# WT-312.net
KiCad netlist of a schematic drawn in Altium Designer
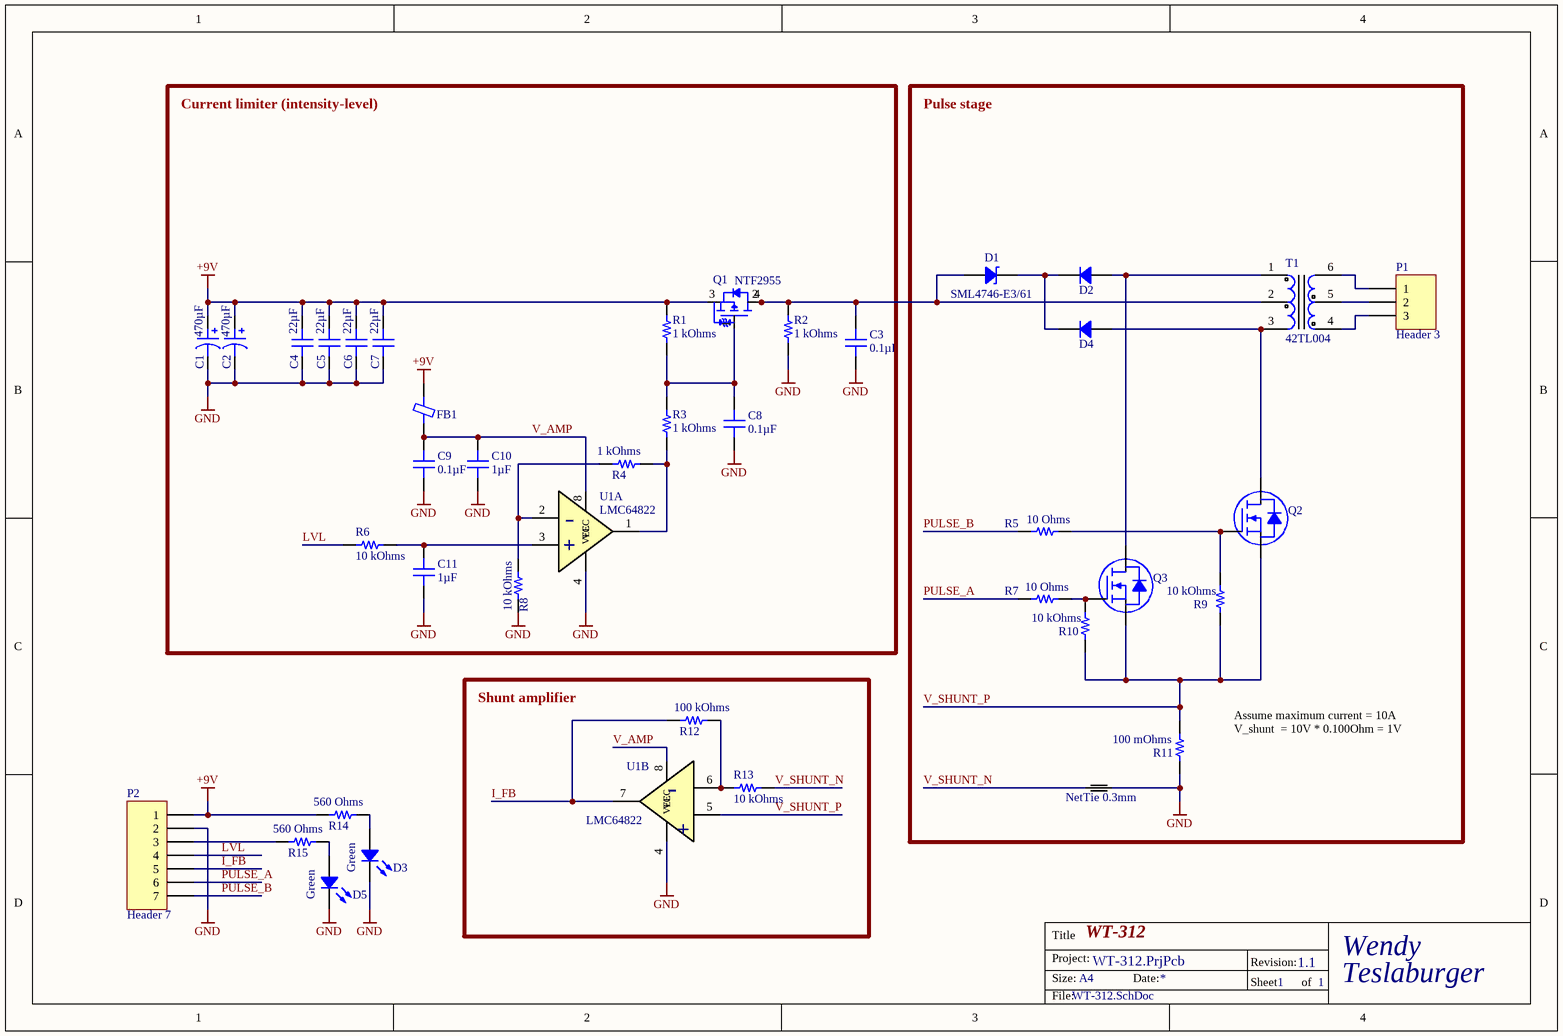
[diagram p0: WT-312.SchDoc]

(export (version "E")
  (design (tool "Eeschema 10.0.6"))
  (components
    (comp (ref "C1")
      (value "470µF")
      (footprint "CAP TH ALUM ELEC D8.00mm S3.50mm H13.00mm")
      (description "CAP ALUM 470UF 20% 16V RADIAL")
      (fields (field (name "PART NUMBER") "477CKE016M") (field (name "MANUFACTURER") "Illinois Capacitor"))
      (libsource (lib "Celestial Altium Library") (part "Polarised Capacitor"))
    )
    (comp (ref "C2")
      (value "470µF")
      (footprint "CAP TH ALUM ELEC D8.00mm S3.50mm H13.00mm")
      (description "CAP ALUM 470UF 20% 16V RADIAL")
      (fields (field (name "PART NUMBER") "477CKE016M") (field (name "MANUFACTURER") "Illinois Capacitor"))
      (libsource (lib "Celestial Altium Library") (part "Polarised Capacitor"))
    )
    (comp (ref "C3")
      (value "0.1µF")
      (footprint "CAP 0603_1608")
      (description "CAP CER 0.1UF 50V X7R 0603")
      (fields (field (name "PART NUMBER") "C0603C104K5RAC7411") (field (name "MANUFACTURER") "KEMET"))
      (libsource (lib "Celestial Altium Library") (part "Capacitor"))
    )
    (comp (ref "C4")
      (value "22µF")
      (footprint "CAP 1210_3225 - 2.8MM")
      (description "CAP CER 22UF 25V X5R 1210")
      (fields (field (name "PART NUMBER") "TMK325BJ226MM-T") (field (name "MANUFACTURER") "Taiyo Yuden"))
      (libsource (lib "Celestial Altium Library") (part "Capacitor"))
    )
    (comp (ref "C5")
      (value "22µF")
      (footprint "CAP 1210_3225 - 2.8MM")
      (description "CAP CER 22UF 25V X5R 1210")
      (fields (field (name "PART NUMBER") "TMK325BJ226MM-T") (field (name "MANUFACTURER") "Taiyo Yuden"))
      (libsource (lib "Celestial Altium Library") (part "Capacitor"))
    )
    (comp (ref "C6")
      (value "22µF")
      (footprint "CAP 1210_3225 - 2.8MM")
      (description "CAP CER 22UF 25V X5R 1210")
      (fields (field (name "PART NUMBER") "TMK325BJ226MM-T") (field (name "MANUFACTURER") "Taiyo Yuden"))
      (libsource (lib "Celestial Altium Library") (part "Capacitor"))
    )
    (comp (ref "C7")
      (value "22µF")
      (footprint "CAP 1210_3225 - 2.8MM")
      (description "CAP CER 22UF 25V X5R 1210")
      (fields (field (name "PART NUMBER") "TMK325BJ226MM-T") (field (name "MANUFACTURER") "Taiyo Yuden"))
      (libsource (lib "Celestial Altium Library") (part "Capacitor"))
    )
    (comp (ref "C8")
      (value "0.1µF")
      (footprint "CAP 0603_1608")
      (description "CAP CER 0.1UF 50V X7R 0603")
      (fields (field (name "PART NUMBER") "C0603C104K5RAC7411") (field (name "MANUFACTURER") "KEMET"))
      (libsource (lib "Celestial Altium Library") (part "Capacitor"))
    )
    (comp (ref "C9")
      (value "0.1µF")
      (footprint "CAP 0603_1608")
      (description "CAP CER 0.1UF 50V X7R 0603")
      (fields (field (name "PART NUMBER") "C0603C104K5RAC7411") (field (name "MANUFACTURER") "KEMET"))
      (libsource (lib "Celestial Altium Library") (part "Capacitor"))
    )
    (comp (ref "C10")
      (value "1µF")
      (footprint "CAP 0603_1608")
      (description "CAP CER 1UF 25V X7R 0603")
      (fields (field (name "PART NUMBER") "TMJ107CB7105KAHR") (field (name "MANUFACTURER") "Taiyo Yuden"))
      (libsource (lib "Celestial Altium Library") (part "Capacitor"))
    )
    (comp (ref "C11")
      (value "1µF")
      (footprint "CAP 0603_1608")
      (description "CAP CER 1UF 25V X7R 0603")
      (fields (field (name "PART NUMBER") "TMJ107CB7105KAHR") (field (name "MANUFACTURER") "Taiyo Yuden"))
      (libsource (lib "Celestial Altium Library") (part "Capacitor"))
    )
    (comp (ref "D1")
      (value "SML4746-E3/61")
      (footprint "DO214AC SMA")
      (description "DIODE ZENER 18V 1W DO214AC")
      (fields
        (field (name "MANUFACTURER") "Vishay Semiconductor Diodes Division")
        (field (name "TOLERANCE") "±10%")
      )
      (libsource (lib "Celestial Altium Library") (part "Diode Zener"))
    )
    (comp (ref "D2")
      (value "DSS14UTR")
      (footprint "SOD123F")
      (description "SCHOTTKY 40V SOD-123FL")
      (fields (field (name "MANUFACTURER") "SMC Diode Solutions"))
      (libsource (lib "Celestial Altium Library") (part "Diode"))
    )
    (comp (ref "D3")
      (value "Green")
      (footprint "LED 1206_3216 GREEN")
      (description "LED GREEN CLEAR 2SMD")
      (fields (field (name "PART NUMBER") "APTD3216LCGCK") (field (name "MANUFACTURER") "Kingbright"))
      (libsource (lib "Celestial Altium Library") (part "LED"))
    )
    (comp (ref "D4")
      (value "DSS14UTR")
      (footprint "SOD123F")
      (description "SCHOTTKY 40V SOD-123FL")
      (fields (field (name "MANUFACTURER") "SMC Diode Solutions"))
      (libsource (lib "Celestial Altium Library") (part "Diode"))
    )
    (comp (ref "D5")
      (value "Green")
      (footprint "LED 1206_3216 GREEN")
      (description "LED GREEN CLEAR 2SMD")
      (fields (field (name "PART NUMBER") "APTD3216LCGCK") (field (name "MANUFACTURER") "Kingbright"))
      (libsource (lib "Celestial Altium Library") (part "LED"))
    )
    (comp (ref "FB1")
      (value "100 Ohms @ 100MHz")
      (footprint "FER 0603_1608")
      (description "FERRITE BEAD 100 OHM 0603 1LN")
      (fields
        (field (name "PART NUMBER") "BLM18KG101TN1D")
        (field (name "MANUFACTURER") "Murata Electronics")
      )
      (libsource (lib "Celestial Altium Library") (part "Ferrite Chip"))
    )
    (comp (ref "NT")
      (value "NetTie 0.3mm")
      (footprint "NetTie0.3mm")
      (libsource (lib "7c7_Passives") (part "NetTie_0.3mm"))
    )
    (comp (ref "P1")
      (value "Header 3")
      (footprint "HDR1X3")
      (description "Header, 3-Pin")
      (fields (field (name "PUBLISHER") "Altium Limited"))
      (libsource (lib "Miscellaneous Connectors") (part "Header 3"))
    )
    (comp (ref "P2")
      (value "Header 7")
      (footprint "HDR1X7")
      (description "Header, 7-Pin")
      (fields (field (name "PUBLISHER") "Altium Limited"))
      (libsource (lib "Miscellaneous Connectors") (part "Header 7"))
    )
    (comp (ref "Q1")
      (value "NTF2955")
      (footprint "SOT230P700X175-4N")
      (description "Single, P-Channel, SOT-223 -60 V, -2.6 A")
      (libsource (lib "7c7_discretes") (part "NTF2955"))
    )
    (comp (ref "Q2")
      (value "DMN2041L-7")
      (footprint "DIODES SOT-23-3")
      (description "MOSFET N-CH 20V 6.4A SOT23")
      (fields (field (name "MANUFACTURER") "Diodes Incorporated"))
      (libsource (lib "Celestial Altium Library") (part "DIODES INC MOSFET N-CH SOT-23-3"))
    )
    (comp (ref "Q3")
      (value "DMN2041L-7")
      (footprint "DIODES SOT-23-3")
      (description "MOSFET N-CH 20V 6.4A SOT23")
      (fields (field (name "MANUFACTURER") "Diodes Incorporated"))
      (libsource (lib "Celestial Altium Library") (part "DIODES INC MOSFET N-CH SOT-23-3"))
    )
    (comp (ref "R1")
      (value "1 kOhms")
      (footprint "RES 0603_1608")
      (description "RES SMD 1K OHM 1% 1/10W 0603")
      (fields (field (name "PART NUMBER") "CRCW06031K00FKTA") (field (name "MANUFACTURER") "Vishay Dale"))
      (libsource (lib "Celestial Altium Library") (part "Resistor"))
    )
    (comp (ref "R2")
      (value "1 kOhms")
      (footprint "RES 0603_1608")
      (description "RES SMD 1K OHM 1% 1/10W 0603")
      (fields (field (name "PART NUMBER") "CRCW06031K00FKTA") (field (name "MANUFACTURER") "Vishay Dale"))
      (libsource (lib "Celestial Altium Library") (part "Resistor"))
    )
    (comp (ref "R3")
      (value "1 kOhms")
      (footprint "RES 0603_1608")
      (description "RES SMD 1K OHM 1% 1/10W 0603")
      (fields (field (name "PART NUMBER") "CRCW06031K00FKTA") (field (name "MANUFACTURER") "Vishay Dale"))
      (libsource (lib "Celestial Altium Library") (part "Resistor"))
    )
    (comp (ref "R4")
      (value "1 kOhms")
      (footprint "RES 0603_1608")
      (description "RES SMD 1K OHM 1% 1/10W 0603")
      (fields (field (name "PART NUMBER") "CRCW06031K00FKTA") (field (name "MANUFACTURER") "Vishay Dale"))
      (libsource (lib "Celestial Altium Library") (part "Resistor"))
    )
    (comp (ref "R5")
      (value "10 Ohms")
      (footprint "RES 0603_1608")
      (description "RES SMD 10 OHM 1% 1/10W 0603")
      (fields (field (name "PART NUMBER") "AC0603FR-0710RL") (field (name "MANUFACTURER") "Yageo"))
      (libsource (lib "Celestial Altium Library") (part "Resistor"))
    )
    (comp (ref "R6")
      (value "10 kOhms")
      (footprint "RES 0603_1608")
      (description "RES 10K OHM 1% 1/10W 0603")
      (fields
        (field (name "PART NUMBER") "RN73H1JTTD1002F100")
        (field (name "MANUFACTURER") "KOA Speer Electronics, Inc.")
      )
      (libsource (lib "Celestial Altium Library") (part "Resistor"))
    )
    (comp (ref "R7")
      (value "10 Ohms")
      (footprint "RES 0603_1608")
      (description "RES SMD 10 OHM 1% 1/10W 0603")
      (fields (field (name "PART NUMBER") "AC0603FR-0710RL") (field (name "MANUFACTURER") "Yageo"))
      (libsource (lib "Celestial Altium Library") (part "Resistor"))
    )
    (comp (ref "R8")
      (value "10 kOhms")
      (footprint "RES 0603_1608")
      (description "RES 10K OHM 1% 1/10W 0603")
      (fields
        (field (name "PART NUMBER") "RN73H1JTTD1002F100")
        (field (name "MANUFACTURER") "KOA Speer Electronics, Inc.")
      )
      (libsource (lib "Celestial Altium Library") (part "Resistor"))
    )
    (comp (ref "R9")
      (value "10 kOhms")
      (footprint "RES 0603_1608")
      (description "RES 10K OHM 1% 1/10W 0603")
      (fields
        (field (name "PART NUMBER") "RN73H1JTTD1002F100")
        (field (name "MANUFACTURER") "KOA Speer Electronics, Inc.")
      )
      (libsource (lib "Celestial Altium Library") (part "Resistor"))
    )
    (comp (ref "R10")
      (value "10 kOhms")
      (footprint "RES 0603_1608")
      (description "RES 10K OHM 1% 1/10W 0603")
      (fields
        (field (name "PART NUMBER") "RN73H1JTTD1002F100")
        (field (name "MANUFACTURER") "KOA Speer Electronics, Inc.")
      )
      (libsource (lib "Celestial Altium Library") (part "Resistor"))
    )
    (comp (ref "R11")
      (value "100 mOhms")
      (footprint "RES 1206_3216")
      (description "RES 0.1 OHM 1% 1W 1206")
      (fields
        (field (name "PART NUMBER") "SCRR1206S1-R100F")
        (field (name "MANUFACTURER") "Delta Electronics/Cyntec")
      )
      (libsource (lib "Celestial Altium Library") (part "Resistor"))
    )
    (comp (ref "R12")
      (value "100 kOhms")
      (footprint "RES 0603_1608")
      (description "RES SMD 100K OHM 1% 1/10W 0603")
      (fields (field (name "PART NUMBER") "CRCW0603100KFKEA") (field (name "MANUFACTURER") "Vishay Dale"))
      (libsource (lib "Celestial Altium Library") (part "Resistor"))
    )
    (comp (ref "R13")
      (value "10 kOhms")
      (footprint "RES 0603_1608")
      (description "RES 10K OHM 1% 1/10W 0603")
      (fields
        (field (name "PART NUMBER") "RN73H1JTTD1002F100")
        (field (name "MANUFACTURER") "KOA Speer Electronics, Inc.")
      )
      (libsource (lib "Celestial Altium Library") (part "Resistor"))
    )
    (comp (ref "R14")
      (value "560 Ohms")
      (footprint "RES 0603_1608")
      (description "RES SMD 560 OHM 1% 1/10W 0603")
      (fields (field (name "PART NUMBER") "CR0603-FX-5600ELF") (field (name "MANUFACTURER") "Bourns Inc."))
      (libsource (lib "Celestial Altium Library") (part "Resistor"))
    )
    (comp (ref "R15")
      (value "560 Ohms")
      (footprint "RES 0603_1608")
      (description "RES SMD 560 OHM 1% 1/10W 0603")
      (fields (field (name "PART NUMBER") "CR0603-FX-5600ELF") (field (name "MANUFACTURER") "Bourns Inc."))
      (libsource (lib "Celestial Altium Library") (part "Resistor"))
    )
    (comp (ref "T1")
      (value "42TL004")
      (footprint "42TL-Series")
      (description "Miniature audio transformer")
      (libsource (lib "Melexis_bot") (part "42LT004"))
    )
    (comp (ref "U1")
      (value "LMC64822")
      (footprint "SOIC127P490X175-8N")
      (description "CMOS Dual Rail-to-Rail Input and Output Operational Amplifier")
      (libsource (lib "") (part "LMC64822_1"))
    )
  )
  (nets
    (net (code "1") (name "+9V") (class "Default")
      (node (ref "C1") (pin "1") (pinfunction "1_1") (pintype "passive"))
      (node (ref "C2") (pin "1") (pinfunction "1_1") (pintype "passive"))
      (node (ref "C4") (pin "2") (pinfunction "2_2") (pintype "passive"))
      (node (ref "C5") (pin "2") (pinfunction "2_2") (pintype "passive"))
      (node (ref "C6") (pin "2") (pinfunction "2_2") (pintype "passive"))
      (node (ref "C7") (pin "2") (pinfunction "2_2") (pintype "passive"))
      (node (ref "FB1") (pin "1") (pinfunction "1_1") (pintype "passive"))
      (node (ref "P2") (pin "1") (pinfunction "1_1") (pintype "passive"))
      (node (ref "Q1") (pin "3") (pinfunction "S_3") (pintype "passive"))
      (node (ref "R1") (pin "1") (pinfunction "1_1") (pintype "passive"))
      (node (ref "R14") (pin "2") (pinfunction "2_2") (pintype "passive"))
    )
    (net (code "2") (name "/I_FB") (class "Default")
      (node (ref "P2") (pin "5") (pinfunction "5_5") (pintype "passive"))
      (node (ref "R12") (pin "1") (pinfunction "1_1") (pintype "passive"))
      (node (ref "U1") (pin "7") (pinfunction "VOUT_7") (pintype "power_in"))
    )
    (net (code "3") (name "/LVL") (class "Default")
      (node (ref "P2") (pin "4") (pinfunction "4_4") (pintype "passive"))
      (node (ref "R6") (pin "2") (pinfunction "2_2") (pintype "passive"))
    )
    (net (code "4") (name "/PULSE_A") (class "Default")
      (node (ref "P2") (pin "6") (pinfunction "6_6") (pintype "passive"))
      (node (ref "R7") (pin "1") (pinfunction "1_1") (pintype "passive"))
    )
    (net (code "5") (name "/PULSE_B") (class "Default")
      (node (ref "P2") (pin "7") (pinfunction "7_7") (pintype "passive"))
      (node (ref "R5") (pin "1") (pinfunction "1_1") (pintype "passive"))
    )
    (net (code "6") (name "/V_AMP") (class "Default")
      (node (ref "C10") (pin "2") (pinfunction "2_2") (pintype "passive"))
      (node (ref "C9") (pin "2") (pinfunction "2_2") (pintype "passive"))
      (node (ref "FB1") (pin "2") (pinfunction "2_2") (pintype "passive"))
      (node (ref "U1") (pin "8") (pinfunction "VCC_8") (pintype "power_in"))
    )
    (net (code "7") (name "/V_SHUNT_N") (class "Default")
      (node (ref "NT") (pin "1") (pinfunction "1_1") (pintype "passive"))
      (node (ref "R13") (pin "1") (pinfunction "1_1") (pintype "passive"))
    )
    (net (code "8") (name "/V_SHUNT_P") (class "Default")
      (node (ref "Q2") (pin "2") (pinfunction "S_2") (pintype "passive"))
      (node (ref "Q3") (pin "2") (pinfunction "S_2") (pintype "passive"))
      (node (ref "R10") (pin "1") (pinfunction "1_1") (pintype "passive"))
      (node (ref "R11") (pin "2") (pinfunction "2_2") (pintype "passive"))
      (node (ref "R9") (pin "1") (pinfunction "1_1") (pintype "passive"))
      (node (ref "U1") (pin "5") (pinfunction "INP_5") (pintype "power_in"))
    )
    (net (code "9") (name "GND") (class "Default")
      (node (ref "C1") (pin "2") (pinfunction "2_2") (pintype "passive"))
      (node (ref "C10") (pin "1") (pinfunction "1_1") (pintype "passive"))
      (node (ref "C11") (pin "1") (pinfunction "1_1") (pintype "passive"))
      (node (ref "C2") (pin "2") (pinfunction "2_2") (pintype "passive"))
      (node (ref "C3") (pin "1") (pinfunction "1_1") (pintype "passive"))
      (node (ref "C4") (pin "1") (pinfunction "1_1") (pintype "passive"))
      (node (ref "C5") (pin "1") (pinfunction "1_1") (pintype "passive"))
      (node (ref "C6") (pin "1") (pinfunction "1_1") (pintype "passive"))
      (node (ref "C7") (pin "1") (pinfunction "1_1") (pintype "passive"))
      (node (ref "C8") (pin "1") (pinfunction "1_1") (pintype "passive"))
      (node (ref "C9") (pin "1") (pinfunction "1_1") (pintype "passive"))
      (node (ref "D3") (pin "2") (pinfunction "2_2") (pintype "passive"))
      (node (ref "D5") (pin "2") (pinfunction "2_2") (pintype "passive"))
      (node (ref "NT") (pin "2") (pinfunction "2_2") (pintype "passive"))
      (node (ref "P2") (pin "2") (pinfunction "2_2") (pintype "passive"))
      (node (ref "R11") (pin "1") (pinfunction "1_1") (pintype "passive"))
      (node (ref "R2") (pin "2") (pinfunction "2_2") (pintype "passive"))
      (node (ref "R8") (pin "1") (pinfunction "1_1") (pintype "passive"))
      (node (ref "U1") (pin "4") (pinfunction "VEE_4") (pintype "power_in"))
    )
    (net (code "10") (name "Net-(D1-Pad2)") (class "Default")
      (node (ref "D1") (pin "2") (pinfunction "2_2") (pintype "passive"))
      (node (ref "D2") (pin "2") (pinfunction "2_2") (pintype "passive"))
      (node (ref "D4") (pin "2") (pinfunction "2_2") (pintype "passive"))
    )
    (net (code "11") (name "Net-(D3-Pad1)") (class "Default")
      (node (ref "D3") (pin "1") (pinfunction "1_1") (pintype "passive"))
      (node (ref "R14") (pin "1") (pinfunction "1_1") (pintype "passive"))
    )
    (net (code "12") (name "Net-(D5-Pad1)") (class "Default")
      (node (ref "D5") (pin "1") (pinfunction "1_1") (pintype "passive"))
      (node (ref "R15") (pin "1") (pinfunction "1_1") (pintype "passive"))
    )
    (net (code "13") (name "Net-(P2-Pad3)") (class "Default")
      (node (ref "P2") (pin "3") (pinfunction "3_3") (pintype "passive"))
      (node (ref "R15") (pin "2") (pinfunction "2_2") (pintype "passive"))
    )
    (net (code "14") (name "Net-(Q1-G)") (class "Default")
      (node (ref "C8") (pin "2") (pinfunction "2_2") (pintype "passive"))
      (node (ref "Q1") (pin "1") (pinfunction "G_1") (pintype "passive"))
      (node (ref "R1") (pin "2") (pinfunction "2_2") (pintype "passive"))
      (node (ref "R3") (pin "1") (pinfunction "1_1") (pintype "passive"))
    )
    (net (code "15") (name "Net-(Q2-D)") (class "Default")
      (node (ref "D4") (pin "1") (pinfunction "1_1") (pintype "passive"))
      (node (ref "Q2") (pin "3") (pinfunction "D_3") (pintype "passive"))
      (node (ref "T1") (pin "3") (pinfunction "Pri_L_3") (pintype "power_in"))
    )
    (net (code "16") (name "Net-(Q2-G)") (class "Default")
      (node (ref "Q2") (pin "1") (pinfunction "G_1") (pintype "passive"))
      (node (ref "R5") (pin "2") (pinfunction "2_2") (pintype "passive"))
      (node (ref "R9") (pin "2") (pinfunction "2_2") (pintype "passive"))
    )
    (net (code "17") (name "Net-(Q3-D)") (class "Default")
      (node (ref "D2") (pin "1") (pinfunction "1_1") (pintype "passive"))
      (node (ref "Q3") (pin "3") (pinfunction "D_3") (pintype "passive"))
      (node (ref "T1") (pin "1") (pinfunction "Pri_H_1") (pintype "power_in"))
    )
    (net (code "18") (name "Net-(Q3-G)") (class "Default")
      (node (ref "Q3") (pin "1") (pinfunction "G_1") (pintype "passive"))
      (node (ref "R10") (pin "2") (pinfunction "2_2") (pintype "passive"))
      (node (ref "R7") (pin "2") (pinfunction "2_2") (pintype "passive"))
    )
    (net (code "19") (name "Net-(T1-Pri_C)") (class "Default")
      (node (ref "C3") (pin "2") (pinfunction "2_2") (pintype "passive"))
      (node (ref "D1") (pin "1") (pinfunction "1_1") (pintype "passive"))
      (node (ref "Q1") (pin "2") (pinfunction "D_2") (pintype "passive"))
      (node (ref "Q1") (pin "4") (pinfunction "D_4") (pintype "passive"))
      (node (ref "R2") (pin "1") (pinfunction "1_1") (pintype "passive"))
      (node (ref "T1") (pin "2") (pinfunction "Pri_C_2") (pintype "power_in"))
    )
    (net (code "20") (name "Net-(T1-Sec_C)") (class "Default")
      (node (ref "P1") (pin "2") (pinfunction "2_2") (pintype "passive"))
      (node (ref "T1") (pin "5") (pinfunction "Sec_C_5") (pintype "power_in"))
    )
    (net (code "21") (name "Net-(T1-Sec_H)") (class "Default")
      (node (ref "P1") (pin "1") (pinfunction "1_1") (pintype "passive"))
      (node (ref "T1") (pin "6") (pinfunction "Sec_H_6") (pintype "power_in"))
    )
    (net (code "22") (name "Net-(T1-Sec_L)") (class "Default")
      (node (ref "P1") (pin "3") (pinfunction "3_3") (pintype "passive"))
      (node (ref "T1") (pin "4") (pinfunction "Sec_L_4") (pintype "power_in"))
    )
    (net (code "23") (name "Net-(U1A-INN)") (class "Default")
      (node (ref "R4") (pin "2") (pinfunction "2_2") (pintype "passive"))
      (node (ref "R8") (pin "2") (pinfunction "2_2") (pintype "passive"))
      (node (ref "U1") (pin "2") (pinfunction "INN_2") (pintype "power_in"))
    )
    (net (code "24") (name "Net-(U1A-INP)") (class "Default")
      (node (ref "C11") (pin "2") (pinfunction "2_2") (pintype "passive"))
      (node (ref "R6") (pin "1") (pinfunction "1_1") (pintype "passive"))
      (node (ref "U1") (pin "3") (pinfunction "INP_3") (pintype "power_in"))
    )
    (net (code "25") (name "Net-(U1A-VOUT)") (class "Default")
      (node (ref "R3") (pin "2") (pinfunction "2_2") (pintype "passive"))
      (node (ref "R4") (pin "1") (pinfunction "1_1") (pintype "passive"))
      (node (ref "U1") (pin "1") (pinfunction "VOUT_1") (pintype "power_in"))
    )
    (net (code "26") (name "Net-(U1B-INN)") (class "Default")
      (node (ref "R12") (pin "2") (pinfunction "2_2") (pintype "passive"))
      (node (ref "R13") (pin "2") (pinfunction "2_2") (pintype "passive"))
      (node (ref "U1") (pin "6") (pinfunction "INN_6") (pintype "power_in"))
    )
  )
)
